# Obstacle_Detection.net
KiCad netlist of a schematic drawn in EAGLE
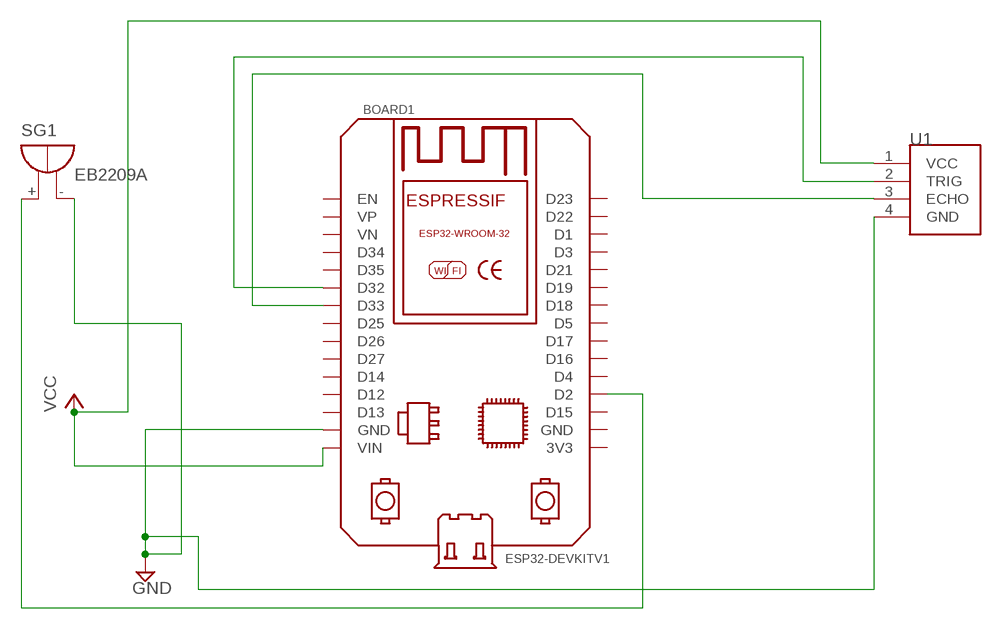
[diagram p0: schematic, sheet 1]

(export (version "E")
  (design (tool "Eeschema 10.0.6"))
  (components
    (comp (ref "BOARD1")
      (value "ESP32DEVKITV1")
      (footprint "eagle-import:ESP32-DEVKITV1")
      (libsource (lib "eagle-import") (part "ESP32DEVKITV1"))
    )
    (comp (ref "SG1")
      (value "EB2209A")
      (footprint "eagle-import:EB2209A")
      (libsource (lib "eagle-import") (part "EB2209A"))
    )
    (comp (ref "U1")
      (value "HC-SR04")
      (footprint "eagle-import:XCVR_HC-SR04")
      (fields (field (name "MF") "SparkFun Electronics"))
      (libsource (lib "eagle-import") (part "HC-SR04"))
    )
  )
  (nets
    (net (code "1") (name "GND") (class "Default")
      (node (ref "BOARD1") (pin "GND") (pinfunction "GND_GND") (pintype "bidirectional"))
      (node (ref "SG1") (pin "-") (pinfunction "-_-") (pintype "passive"))
      (node (ref "U1") (pin "4") (pinfunction "GND_4") (pintype "power_in"))
    )
    (net (code "2") (name "Net-(BOARD1-PadD2)") (class "Default")
      (node (ref "BOARD1") (pin "D2") (pinfunction "D2_D2") (pintype "bidirectional"))
      (node (ref "SG1") (pin "+") (pinfunction "+_+") (pintype "passive"))
    )
    (net (code "3") (name "Net-(U1-ECHO)") (class "Default")
      (node (ref "BOARD1") (pin "D33") (pinfunction "D33_D33") (pintype "bidirectional"))
      (node (ref "U1") (pin "3") (pinfunction "ECHO_3") (pintype "bidirectional"))
    )
    (net (code "4") (name "Net-(U1-TRIG)") (class "Default")
      (node (ref "BOARD1") (pin "D32") (pinfunction "D32_D32") (pintype "bidirectional"))
      (node (ref "U1") (pin "2") (pinfunction "TRIG_2") (pintype "bidirectional"))
    )
    (net (code "5") (name "VCC") (class "Default")
      (node (ref "BOARD1") (pin "VIN") (pinfunction "VIN_VIN") (pintype "bidirectional"))
      (node (ref "U1") (pin "1") (pinfunction "VCC_1") (pintype "power_in"))
    )
    (net (code "6") (name "unconnected-(BOARD1-GND-PadGND@1)") (class "Default")
      (node (ref "BOARD1") (pin "GND@1") (pinfunction "GND_GND@1") (pintype "bidirectional"))
    )
    (net (code "7") (name "unconnected-(BOARD1-Pad3V3)") (class "Default")
      (node (ref "BOARD1") (pin "3V3") (pinfunction "3V3_3V3") (pintype "bidirectional"))
    )
    (net (code "8") (name "unconnected-(BOARD1-PadD1)") (class "Default")
      (node (ref "BOARD1") (pin "D1") (pinfunction "D1_D1") (pintype "bidirectional"))
    )
    (net (code "9") (name "unconnected-(BOARD1-PadD3)") (class "Default")
      (node (ref "BOARD1") (pin "D3") (pinfunction "D3_D3") (pintype "bidirectional"))
    )
    (net (code "10") (name "unconnected-(BOARD1-PadD4)") (class "Default")
      (node (ref "BOARD1") (pin "D4") (pinfunction "D4_D4") (pintype "bidirectional"))
    )
    (net (code "11") (name "unconnected-(BOARD1-PadD5)") (class "Default")
      (node (ref "BOARD1") (pin "D5") (pinfunction "D5_D5") (pintype "bidirectional"))
    )
    (net (code "12") (name "unconnected-(BOARD1-PadD12)") (class "Default")
      (node (ref "BOARD1") (pin "D12") (pinfunction "D12_D12") (pintype "bidirectional"))
    )
    (net (code "13") (name "unconnected-(BOARD1-PadD13)") (class "Default")
      (node (ref "BOARD1") (pin "D13") (pinfunction "D13_D13") (pintype "bidirectional"))
    )
    (net (code "14") (name "unconnected-(BOARD1-PadD14)") (class "Default")
      (node (ref "BOARD1") (pin "D14") (pinfunction "D14_D14") (pintype "bidirectional"))
    )
    (net (code "15") (name "unconnected-(BOARD1-PadD15)") (class "Default")
      (node (ref "BOARD1") (pin "D15") (pinfunction "D15_D15") (pintype "bidirectional"))
    )
    (net (code "16") (name "unconnected-(BOARD1-PadD16)") (class "Default")
      (node (ref "BOARD1") (pin "D16") (pinfunction "D16_D16") (pintype "bidirectional"))
    )
    (net (code "17") (name "unconnected-(BOARD1-PadD17)") (class "Default")
      (node (ref "BOARD1") (pin "D17") (pinfunction "D17_D17") (pintype "bidirectional"))
    )
    (net (code "18") (name "unconnected-(BOARD1-PadD18)") (class "Default")
      (node (ref "BOARD1") (pin "D18") (pinfunction "D18_D18") (pintype "bidirectional"))
    )
    (net (code "19") (name "unconnected-(BOARD1-PadD19)") (class "Default")
      (node (ref "BOARD1") (pin "D19") (pinfunction "D19_D19") (pintype "bidirectional"))
    )
    (net (code "20") (name "unconnected-(BOARD1-PadD21)") (class "Default")
      (node (ref "BOARD1") (pin "D21") (pinfunction "D21_D21") (pintype "bidirectional"))
    )
    (net (code "21") (name "unconnected-(BOARD1-PadD22)") (class "Default")
      (node (ref "BOARD1") (pin "D22") (pinfunction "D22_D22") (pintype "bidirectional"))
    )
    (net (code "22") (name "unconnected-(BOARD1-PadD23)") (class "Default")
      (node (ref "BOARD1") (pin "D23") (pinfunction "D23_D23") (pintype "bidirectional"))
    )
    (net (code "23") (name "unconnected-(BOARD1-PadD25)") (class "Default")
      (node (ref "BOARD1") (pin "D25") (pinfunction "D25_D25") (pintype "bidirectional"))
    )
    (net (code "24") (name "unconnected-(BOARD1-PadD26)") (class "Default")
      (node (ref "BOARD1") (pin "D26") (pinfunction "D26_D26") (pintype "bidirectional"))
    )
    (net (code "25") (name "unconnected-(BOARD1-PadD27)") (class "Default")
      (node (ref "BOARD1") (pin "D27") (pinfunction "D27_D27") (pintype "bidirectional"))
    )
    (net (code "26") (name "unconnected-(BOARD1-PadD34)") (class "Default")
      (node (ref "BOARD1") (pin "D34") (pinfunction "D34_D34") (pintype "bidirectional"))
    )
    (net (code "27") (name "unconnected-(BOARD1-PadD35)") (class "Default")
      (node (ref "BOARD1") (pin "D35") (pinfunction "D35_D35") (pintype "bidirectional"))
    )
    (net (code "28") (name "unconnected-(BOARD1-PadEN)") (class "Default")
      (node (ref "BOARD1") (pin "EN") (pinfunction "EN_EN") (pintype "bidirectional"))
    )
    (net (code "29") (name "unconnected-(BOARD1-PadVN)") (class "Default")
      (node (ref "BOARD1") (pin "VN") (pinfunction "VN_VN") (pintype "bidirectional"))
    )
    (net (code "30") (name "unconnected-(BOARD1-PadVP)") (class "Default")
      (node (ref "BOARD1") (pin "VP") (pinfunction "VP_VP") (pintype "bidirectional"))
    )
  )
)
